# PWM_LOGIC.net
KiCad netlist of a schematic drawn in Altium Designer
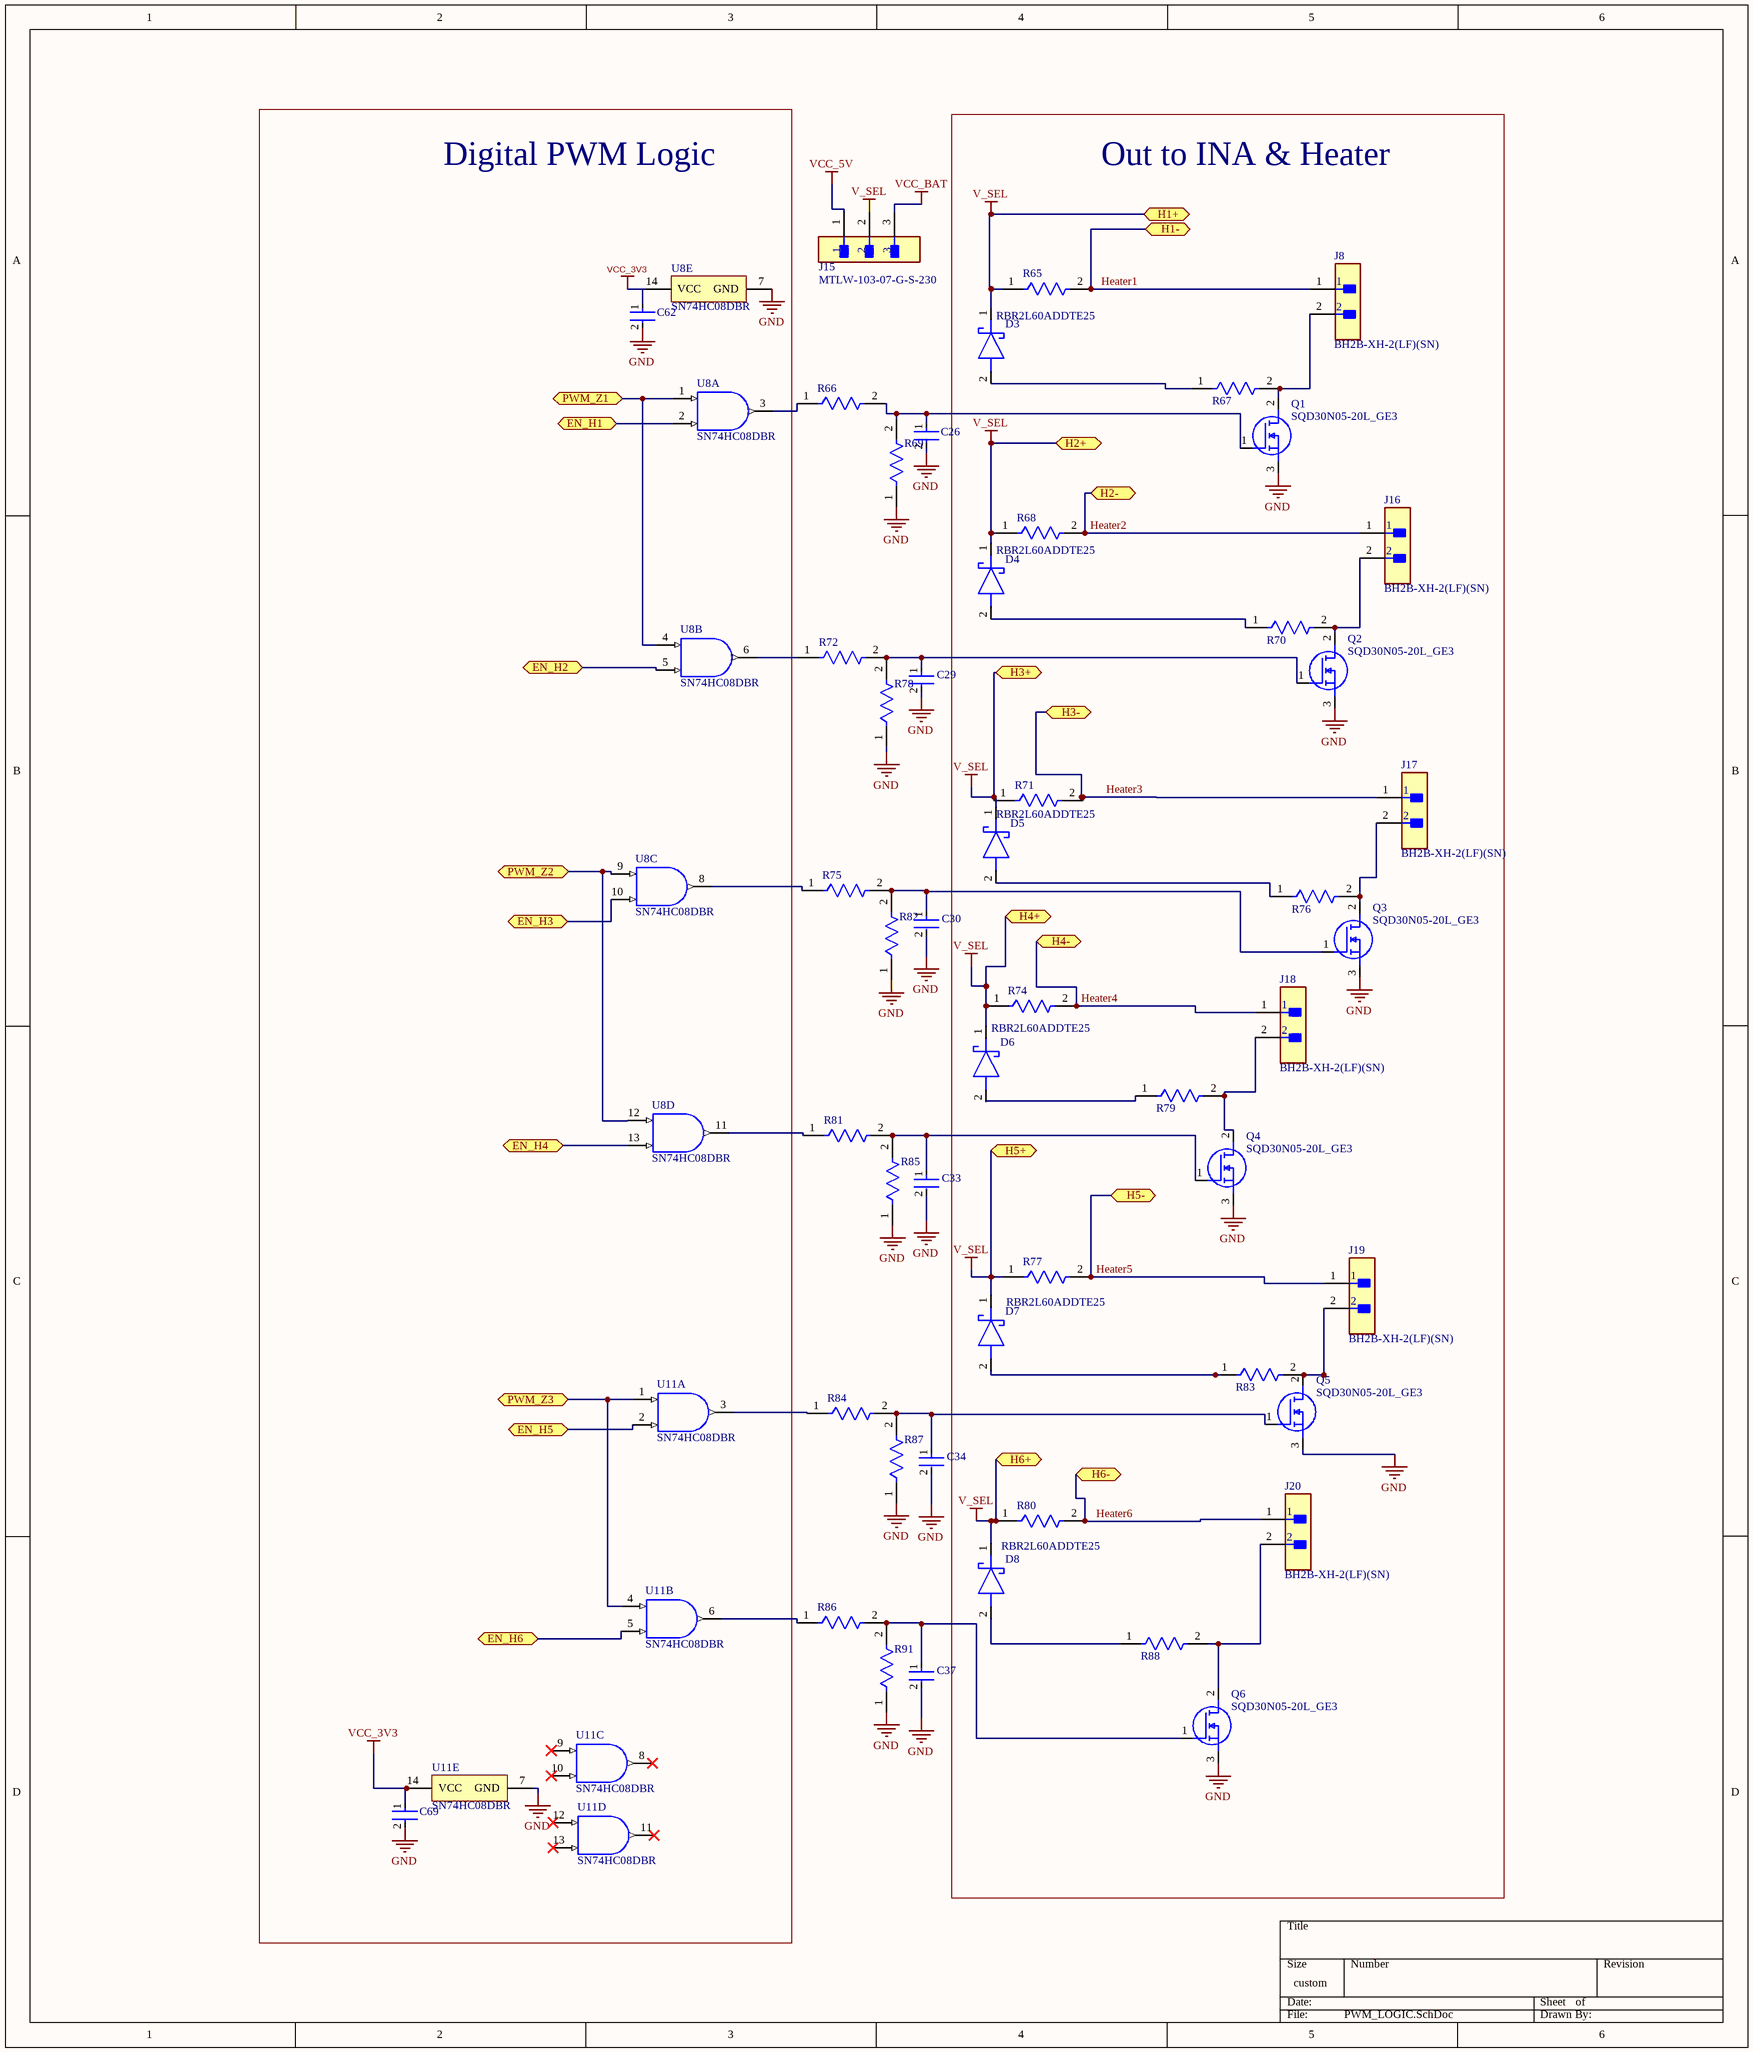
[diagram p0: PWM_LOGIC.SchDoc]

(export (version "E")
  (design (tool "Eeschema 10.0.6"))
  (components
    (comp (ref "C26")
      (value "C0603C472K3RACAUTO")
      (footprint "FP-C0603C-CF-MFG")
      (description "C0603 4,700 pF X7R 30ppm/°C 10.00% 25 V")
      (fields
        (field (name "TOLERANCE") "0.1")
        (field (name "OCTOPART") "https://octopart.com/c0603c472k3racauto-kemet-22128797")
      )
      (libsource (lib "Altium Content Vault") (part "b4654b650e69147ec39a6b967a45e02"))
    )
    (comp (ref "C29")
      (value "C0603C472K3RACAUTO")
      (footprint "FP-C0603C-CF-MFG")
      (description "C0603 4,700 pF X7R 30ppm/°C 10.00% 25 V")
      (fields
        (field (name "TOLERANCE") "0.1")
        (field (name "OCTOPART") "https://octopart.com/c0603c472k3racauto-kemet-22128797")
      )
      (libsource (lib "Altium Content Vault") (part "b4654b650e69147ec39a6b967a45e02"))
    )
    (comp (ref "C30")
      (value "C0603C472K3RACAUTO")
      (footprint "FP-C0603C-CF-MFG")
      (description "C0603 4,700 pF X7R 30ppm/°C 10.00% 25 V")
      (fields
        (field (name "TOLERANCE") "0.1")
        (field (name "OCTOPART") "https://octopart.com/c0603c472k3racauto-kemet-22128797")
      )
      (libsource (lib "Altium Content Vault") (part "b4654b650e69147ec39a6b967a45e02"))
    )
    (comp (ref "C33")
      (value "C0603C472K3RACAUTO")
      (footprint "FP-C0603C-CF-MFG")
      (description "C0603 4,700 pF X7R 30ppm/°C 10.00% 25 V")
      (fields
        (field (name "TOLERANCE") "0.1")
        (field (name "OCTOPART") "https://octopart.com/c0603c472k3racauto-kemet-22128797")
      )
      (libsource (lib "Altium Content Vault") (part "b4654b650e69147ec39a6b967a45e02"))
    )
    (comp (ref "C34")
      (value "C0603C472K3RACAUTO")
      (footprint "FP-C0603C-CF-MFG")
      (description "C0603 4,700 pF X7R 30ppm/°C 10.00% 25 V")
      (fields
        (field (name "TOLERANCE") "0.1")
        (field (name "OCTOPART") "https://octopart.com/c0603c472k3racauto-kemet-22128797")
      )
      (libsource (lib "Altium Content Vault") (part "b4654b650e69147ec39a6b967a45e02"))
    )
    (comp (ref "C37")
      (value "C0603C472K3RACAUTO")
      (footprint "FP-C0603C-CF-MFG")
      (description "C0603 4,700 pF X7R 30ppm/°C 10.00% 25 V")
      (fields
        (field (name "TOLERANCE") "0.1")
        (field (name "OCTOPART") "https://octopart.com/c0603c472k3racauto-kemet-22128797")
      )
      (libsource (lib "Altium Content Vault") (part "b4654b650e69147ec39a6b967a45e02"))
    )
    (comp (ref "C62")
      (value "GRM033C71A104KE14J")
      (footprint "FP-GRM033-0_03-MFG")
      (description "Chip Multilayer Ceramic Capacitors for General Purpose, 0201, 0.10uF, X7S, 22%, 10%, 10V")
      (fields (field (name "TOLERANCE") "10%"))
      (libsource (lib "Altium Content Vault") (part "b4654b650e69147ec39a6b967a45e02"))
    )
    (comp (ref "C69")
      (value "GRM033C71A104KE14J")
      (footprint "FP-GRM033-0_03-MFG")
      (description "Chip Multilayer Ceramic Capacitors for General Purpose, 0201, 0.10uF, X7S, 22%, 10%, 10V")
      (fields (field (name "TOLERANCE") "10%"))
      (libsource (lib "Altium Content Vault") (part "b4654b650e69147ec39a6b967a45e02"))
    )
    (comp (ref "D3")
      (value "RBR2L60ADDTE25")
      (footprint "SamacSys:DIOM5026X220N")
      (description "Schottky Diode")
      (fields (field (name "MOUSER PART NUMBER") "755-RBR2L60ADDTE25"))
      (libsource (lib "*") (part "RBR2L60ADDTE25"))
    )
    (comp (ref "D4")
      (value "RBR2L60ADDTE25")
      (footprint "SamacSys:DIOM5026X220N")
      (description "Schottky Diode")
      (fields (field (name "MOUSER PART NUMBER") "755-RBR2L60ADDTE25"))
      (libsource (lib "*") (part "RBR2L60ADDTE25"))
    )
    (comp (ref "D5")
      (value "RBR2L60ADDTE25")
      (footprint "SamacSys:DIOM5026X220N")
      (description "Schottky Diode")
      (fields (field (name "MOUSER PART NUMBER") "755-RBR2L60ADDTE25"))
      (libsource (lib "*") (part "RBR2L60ADDTE25"))
    )
    (comp (ref "D6")
      (value "RBR2L60ADDTE25")
      (footprint "SamacSys:DIOM5026X220N")
      (description "Schottky Diode")
      (fields (field (name "MOUSER PART NUMBER") "755-RBR2L60ADDTE25"))
      (libsource (lib "*") (part "RBR2L60ADDTE25"))
    )
    (comp (ref "D7")
      (value "RBR2L60ADDTE25")
      (footprint "SamacSys:DIOM5026X220N")
      (description "Schottky Diode")
      (fields (field (name "MOUSER PART NUMBER") "755-RBR2L60ADDTE25"))
      (libsource (lib "*") (part "RBR2L60ADDTE25"))
    )
    (comp (ref "D8")
      (value "RBR2L60ADDTE25")
      (footprint "SamacSys:DIOM5026X220N")
      (description "Schottky Diode")
      (fields (field (name "MOUSER PART NUMBER") "755-RBR2L60ADDTE25"))
      (libsource (lib "*") (part "RBR2L60ADDTE25"))
    )
    (comp (ref "J8")
      (value "BH2B-XH-2(LF)(SN)")
      (footprint "FP-BH2B-XH-2_LF_SN-MFG")
      (description "CONN HEADER VERT 2POS 2.5MM")
      (libsource (lib "Altium Content Vault") (part "3bc925449376181038e59eaffc5286c"))
    )
    (comp (ref "J15")
      (value "MTLW-103-07-G-S-230")
      (footprint "FP-MTLW-103-07-G-S-230-MFG")
      (description "CONN HEADER VERT 3POS 2.54MM")
      (libsource (lib "Altium Content Vault") (part "0d3f023dd272f625e17a2be33dea85f"))
    )
    (comp (ref "J16")
      (value "BH2B-XH-2(LF)(SN)")
      (footprint "FP-BH2B-XH-2_LF_SN-MFG")
      (description "CONN HEADER VERT 2POS 2.5MM")
      (libsource (lib "Altium Content Vault") (part "3bc925449376181038e59eaffc5286c"))
    )
    (comp (ref "J17")
      (value "BH2B-XH-2(LF)(SN)")
      (footprint "FP-BH2B-XH-2_LF_SN-MFG")
      (description "CONN HEADER VERT 2POS 2.5MM")
      (libsource (lib "Altium Content Vault") (part "3bc925449376181038e59eaffc5286c"))
    )
    (comp (ref "J18")
      (value "BH2B-XH-2(LF)(SN)")
      (footprint "FP-BH2B-XH-2_LF_SN-MFG")
      (description "CONN HEADER VERT 2POS 2.5MM")
      (libsource (lib "Altium Content Vault") (part "3bc925449376181038e59eaffc5286c"))
    )
    (comp (ref "J19")
      (value "BH2B-XH-2(LF)(SN)")
      (footprint "FP-BH2B-XH-2_LF_SN-MFG")
      (description "CONN HEADER VERT 2POS 2.5MM")
      (libsource (lib "Altium Content Vault") (part "3bc925449376181038e59eaffc5286c"))
    )
    (comp (ref "J20")
      (value "BH2B-XH-2(LF)(SN)")
      (footprint "FP-BH2B-XH-2_LF_SN-MFG")
      (description "CONN HEADER VERT 2POS 2.5MM")
      (libsource (lib "Altium Content Vault") (part "3bc925449376181038e59eaffc5286c"))
    )
    (comp (ref "Q1")
      (value "SQD30N05-20L_GE3")
      (footprint "SamacSys:SQD30N0520L_GE3")
      (description "MOSFET (N-Channel)")
      (fields (field (name "MOUSER PART NUMBER") "78-SQD30N05-20L_GE3"))
      (libsource (lib "*") (part "SQD30N05-20L_GE3"))
    )
    (comp (ref "Q2")
      (value "SQD30N05-20L_GE3")
      (footprint "SamacSys:SQD30N0520L_GE3")
      (description "MOSFET (N-Channel)")
      (fields (field (name "MOUSER PART NUMBER") "78-SQD30N05-20L_GE3"))
      (libsource (lib "*") (part "SQD30N05-20L_GE3"))
    )
    (comp (ref "Q3")
      (value "SQD30N05-20L_GE3")
      (footprint "SamacSys:SQD30N0520L_GE3")
      (description "MOSFET (N-Channel)")
      (fields (field (name "MOUSER PART NUMBER") "78-SQD30N05-20L_GE3"))
      (libsource (lib "*") (part "SQD30N05-20L_GE3"))
    )
    (comp (ref "Q4")
      (value "SQD30N05-20L_GE3")
      (footprint "SamacSys:SQD30N0520L_GE3")
      (description "MOSFET (N-Channel)")
      (fields (field (name "MOUSER PART NUMBER") "78-SQD30N05-20L_GE3"))
      (libsource (lib "*") (part "SQD30N05-20L_GE3"))
    )
    (comp (ref "Q5")
      (value "SQD30N05-20L_GE3")
      (footprint "SamacSys:SQD30N0520L_GE3")
      (description "MOSFET (N-Channel)")
      (fields (field (name "MOUSER PART NUMBER") "78-SQD30N05-20L_GE3"))
      (libsource (lib "*") (part "SQD30N05-20L_GE3"))
    )
    (comp (ref "Q6")
      (value "SQD30N05-20L_GE3")
      (footprint "SamacSys:SQD30N0520L_GE3")
      (description "MOSFET (N-Channel)")
      (fields (field (name "MOUSER PART NUMBER") "78-SQD30N05-20L_GE3"))
      (libsource (lib "*") (part "SQD30N05-20L_GE3"))
    )
    (comp (ref "R65")
      (value "CSR1206FT50L0")
      (footprint "FP-CSR1206-IPC_B")
      (description "General Purpose Thick Film Chip Resistor, 1206, 50mΩ, 1%, 100ppm/°C, 0.5W")
      (fields (field (name "TOLERANCE") "1%"))
      (libsource (lib "Altium Content Vault") (part "1029c3af85768c4190bb7ad29bc67b5"))
    )
    (comp (ref "R66")
      (value "RMCF1210FT330R")
      (footprint "FP-RMCF1210-IPC_B")
      (description "330Ω ±1% 0.5W 1210 Thick Film Chip Resistor AEC-Q200 compliant")
      (fields (field (name "TOLERANCE") "1%"))
      (libsource (lib "Altium Content Vault") (part "1029c3af85768c4190bb7ad29bc67b5"))
    )
    (comp (ref "R67")
      (value "ESR03EZPF75R0")
      (footprint "FP-ESR03-IPC_B")
      (description "75Ω ±1% 0.25W 0603 Anti-Surge Chip Resistor AEC-Q200")
      (fields (field (name "TOLERANCE") "1%"))
      (libsource (lib "Altium Content Vault") (part "1029c3af85768c4190bb7ad29bc67b5"))
    )
    (comp (ref "R68")
      (value "CSR1206FT50L0")
      (footprint "FP-CSR1206-IPC_B")
      (description "General Purpose Thick Film Chip Resistor, 1206, 50mΩ, 1%, 100ppm/°C, 0.5W")
      (fields (field (name "TOLERANCE") "1%"))
      (libsource (lib "Altium Content Vault") (part "1029c3af85768c4190bb7ad29bc67b5"))
    )
    (comp (ref "R69")
      (value "RMCF1206FG10K0")
      (footprint "FP-RMCF1206-MFG")
      (description "10kΩ ±1% 0.25W 1206 Thick Film Chip Resistor AEC-Q200 compliant")
      (fields (field (name "TOLERANCE") "1%"))
      (libsource (lib "Altium Content Vault") (part "1029c3af85768c4190bb7ad29bc67b5"))
    )
    (comp (ref "R70")
      (value "ESR03EZPF75R0")
      (footprint "FP-ESR03-IPC_B")
      (description "75Ω ±1% 0.25W 0603 Anti-Surge Chip Resistor AEC-Q200")
      (fields (field (name "TOLERANCE") "1%"))
      (libsource (lib "Altium Content Vault") (part "1029c3af85768c4190bb7ad29bc67b5"))
    )
    (comp (ref "R71")
      (value "CSR1206FT50L0")
      (footprint "FP-CSR1206-IPC_B")
      (description "General Purpose Thick Film Chip Resistor, 1206, 50mΩ, 1%, 100ppm/°C, 0.5W")
      (fields (field (name "TOLERANCE") "1%"))
      (libsource (lib "Altium Content Vault") (part "1029c3af85768c4190bb7ad29bc67b5"))
    )
    (comp (ref "R72")
      (value "RMCF1210FT330R")
      (footprint "FP-RMCF1210-IPC_B")
      (description "330Ω ±1% 0.5W 1210 Thick Film Chip Resistor AEC-Q200 compliant")
      (fields (field (name "TOLERANCE") "1%"))
      (libsource (lib "Altium Content Vault") (part "1029c3af85768c4190bb7ad29bc67b5"))
    )
    (comp (ref "R74")
      (value "CSR1206FT50L0")
      (footprint "FP-CSR1206-IPC_B")
      (description "General Purpose Thick Film Chip Resistor, 1206, 50mΩ, 1%, 100ppm/°C, 0.5W")
      (fields (field (name "TOLERANCE") "1%"))
      (libsource (lib "Altium Content Vault") (part "1029c3af85768c4190bb7ad29bc67b5"))
    )
    (comp (ref "R75")
      (value "RMCF1210FT330R")
      (footprint "FP-RMCF1210-IPC_B")
      (description "330Ω ±1% 0.5W 1210 Thick Film Chip Resistor AEC-Q200 compliant")
      (fields (field (name "TOLERANCE") "1%"))
      (libsource (lib "Altium Content Vault") (part "1029c3af85768c4190bb7ad29bc67b5"))
    )
    (comp (ref "R76")
      (value "ESR03EZPF75R0")
      (footprint "FP-ESR03-IPC_B")
      (description "75Ω ±1% 0.25W 0603 Anti-Surge Chip Resistor AEC-Q200")
      (fields (field (name "TOLERANCE") "1%"))
      (libsource (lib "Altium Content Vault") (part "1029c3af85768c4190bb7ad29bc67b5"))
    )
    (comp (ref "R77")
      (value "CSR1206FT50L0")
      (footprint "FP-CSR1206-IPC_B")
      (description "General Purpose Thick Film Chip Resistor, 1206, 50mΩ, 1%, 100ppm/°C, 0.5W")
      (fields (field (name "TOLERANCE") "1%"))
      (libsource (lib "Altium Content Vault") (part "1029c3af85768c4190bb7ad29bc67b5"))
    )
    (comp (ref "R78")
      (value "RMCF1206FG10K0")
      (footprint "FP-RMCF1206-MFG")
      (description "10kΩ ±1% 0.25W 1206 Thick Film Chip Resistor AEC-Q200 compliant")
      (fields (field (name "TOLERANCE") "1%"))
      (libsource (lib "Altium Content Vault") (part "1029c3af85768c4190bb7ad29bc67b5"))
    )
    (comp (ref "R79")
      (value "ESR03EZPF75R0")
      (footprint "FP-ESR03-IPC_B")
      (description "75Ω ±1% 0.25W 0603 Anti-Surge Chip Resistor AEC-Q200")
      (fields (field (name "TOLERANCE") "1%"))
      (libsource (lib "Altium Content Vault") (part "1029c3af85768c4190bb7ad29bc67b5"))
    )
    (comp (ref "R80")
      (value "CSR1206FT50L0")
      (footprint "FP-CSR1206-IPC_B")
      (description "General Purpose Thick Film Chip Resistor, 1206, 50mΩ, 1%, 100ppm/°C, 0.5W")
      (fields (field (name "TOLERANCE") "1%"))
      (libsource (lib "Altium Content Vault") (part "1029c3af85768c4190bb7ad29bc67b5"))
    )
    (comp (ref "R81")
      (value "RMCF1210FT330R")
      (footprint "FP-RMCF1210-IPC_B")
      (description "330Ω ±1% 0.5W 1210 Thick Film Chip Resistor AEC-Q200 compliant")
      (fields (field (name "TOLERANCE") "1%"))
      (libsource (lib "Altium Content Vault") (part "1029c3af85768c4190bb7ad29bc67b5"))
    )
    (comp (ref "R82")
      (value "RMCF1206FG10K0")
      (footprint "FP-RMCF1206-MFG")
      (description "10kΩ ±1% 0.25W 1206 Thick Film Chip Resistor AEC-Q200 compliant")
      (fields (field (name "TOLERANCE") "1%"))
      (libsource (lib "Altium Content Vault") (part "1029c3af85768c4190bb7ad29bc67b5"))
    )
    (comp (ref "R83")
      (value "ESR03EZPF75R0")
      (footprint "FP-ESR03-IPC_B")
      (description "75Ω ±1% 0.25W 0603 Anti-Surge Chip Resistor AEC-Q200")
      (fields (field (name "TOLERANCE") "1%"))
      (libsource (lib "Altium Content Vault") (part "1029c3af85768c4190bb7ad29bc67b5"))
    )
    (comp (ref "R84")
      (value "RMCF1210FT330R")
      (footprint "FP-RMCF1210-IPC_B")
      (description "330Ω ±1% 0.5W 1210 Thick Film Chip Resistor AEC-Q200 compliant")
      (fields (field (name "TOLERANCE") "1%"))
      (libsource (lib "Altium Content Vault") (part "1029c3af85768c4190bb7ad29bc67b5"))
    )
    (comp (ref "R85")
      (value "RMCF1206FG10K0")
      (footprint "FP-RMCF1206-MFG")
      (description "10kΩ ±1% 0.25W 1206 Thick Film Chip Resistor AEC-Q200 compliant")
      (fields (field (name "TOLERANCE") "1%"))
      (libsource (lib "Altium Content Vault") (part "1029c3af85768c4190bb7ad29bc67b5"))
    )
    (comp (ref "R86")
      (value "RMCF1210FT330R")
      (footprint "FP-RMCF1210-IPC_B")
      (description "330Ω ±1% 0.5W 1210 Thick Film Chip Resistor AEC-Q200 compliant")
      (fields (field (name "TOLERANCE") "1%"))
      (libsource (lib "Altium Content Vault") (part "1029c3af85768c4190bb7ad29bc67b5"))
    )
    (comp (ref "R87")
      (value "RMCF1206FG10K0")
      (footprint "FP-RMCF1206-MFG")
      (description "10kΩ ±1% 0.25W 1206 Thick Film Chip Resistor AEC-Q200 compliant")
      (fields (field (name "TOLERANCE") "1%"))
      (libsource (lib "Altium Content Vault") (part "1029c3af85768c4190bb7ad29bc67b5"))
    )
    (comp (ref "R88")
      (value "ESR03EZPF75R0")
      (footprint "FP-ESR03-IPC_B")
      (description "75Ω ±1% 0.25W 0603 Anti-Surge Chip Resistor AEC-Q200")
      (fields (field (name "TOLERANCE") "1%"))
      (libsource (lib "Altium Content Vault") (part "1029c3af85768c4190bb7ad29bc67b5"))
    )
    (comp (ref "R91")
      (value "RMCF1206FG10K0")
      (footprint "FP-RMCF1206-MFG")
      (description "10kΩ ±1% 0.25W 1206 Thick Film Chip Resistor AEC-Q200 compliant")
      (fields (field (name "TOLERANCE") "1%"))
      (libsource (lib "Altium Content Vault") (part "1029c3af85768c4190bb7ad29bc67b5"))
    )
    (comp (ref "U8")
      (value "SN74HC08DBR")
      (footprint "DB0014A_L")
      (description "Quadruple 2-Input Positive-AND Gates, DB0014A, LARGE T&R")
      (fields
        (field (name "MANUFACTURER") "Texas Instruments")
        (field (name "GENERIC PART NUMBER") "SN74HC08")
      )
      (libsource (lib "Altium Content Vault") (part "TI-AND-4-2IN-14"))
    )
    (comp (ref "U11")
      (value "SN74HC08DBR")
      (footprint "DB0014A_L")
      (description "Quadruple 2-Input Positive-AND Gates, DB0014A, LARGE T&R")
      (fields
        (field (name "MANUFACTURER") "Texas Instruments")
        (field (name "GENERIC PART NUMBER") "SN74HC08")
      )
      (libsource (lib "Altium Content Vault") (part "TI-AND-4-2IN-14"))
    )
  )
  (nets
    (net (code "2") (name "/EN_H1") (class "Default")
      (node (ref "U8") (pin "2") (pinfunction "1B_2") (pintype "input"))
    )
    (net (code "3") (name "/EN_H2") (class "Default")
      (node (ref "U8") (pin "5") (pinfunction "2B_5") (pintype "input"))
    )
    (net (code "4") (name "/EN_H3") (class "Default")
      (node (ref "U8") (pin "10") (pinfunction "3B_10") (pintype "input"))
    )
    (net (code "5") (name "/EN_H4") (class "Default")
      (node (ref "U8") (pin "13") (pinfunction "4B_13") (pintype "input"))
    )
    (net (code "6") (name "/EN_H5") (class "Default")
      (node (ref "U11") (pin "2") (pinfunction "1B_2") (pintype "input"))
    )
    (net (code "7") (name "/EN_H6") (class "Default")
      (node (ref "U11") (pin "5") (pinfunction "2B_5") (pintype "input"))
    )
    (net (code "8") (name "/Heater1") (class "Default")
      (node (ref "J8") (pin "1") (pinfunction "1_1") (pintype "passive"))
      (node (ref "R65") (pin "2") (pinfunction "2_2") (pintype "passive"))
    )
    (net (code "9") (name "/Heater2") (class "Default")
      (node (ref "J16") (pin "1") (pinfunction "1_1") (pintype "passive"))
      (node (ref "R68") (pin "2") (pinfunction "2_2") (pintype "passive"))
    )
    (net (code "10") (name "/Heater3") (class "Default")
      (node (ref "J17") (pin "1") (pinfunction "1_1") (pintype "passive"))
      (node (ref "R71") (pin "2") (pinfunction "2_2") (pintype "passive"))
    )
    (net (code "11") (name "/Heater4") (class "Default")
      (node (ref "J18") (pin "1") (pinfunction "1_1") (pintype "passive"))
      (node (ref "R74") (pin "2") (pinfunction "2_2") (pintype "passive"))
    )
    (net (code "12") (name "/Heater5") (class "Default")
      (node (ref "J19") (pin "1") (pinfunction "1_1") (pintype "passive"))
      (node (ref "R77") (pin "2") (pinfunction "2_2") (pintype "passive"))
    )
    (net (code "13") (name "/Heater6") (class "Default")
      (node (ref "J20") (pin "1") (pinfunction "1_1") (pintype "passive"))
      (node (ref "R80") (pin "2") (pinfunction "2_2") (pintype "passive"))
    )
    (net (code "14") (name "/PWM_Z1") (class "Default")
      (node (ref "U8") (pin "1") (pinfunction "1A_1") (pintype "input"))
      (node (ref "U8") (pin "4") (pinfunction "2A_4") (pintype "input"))
    )
    (net (code "15") (name "/PWM_Z2") (class "Default")
      (node (ref "U8") (pin "12") (pinfunction "4A_12") (pintype "input"))
      (node (ref "U8") (pin "9") (pinfunction "3A_9") (pintype "input"))
    )
    (net (code "16") (name "/PWM_Z3") (class "Default")
      (node (ref "U11") (pin "1") (pinfunction "1A_1") (pintype "input"))
      (node (ref "U11") (pin "4") (pinfunction "2A_4") (pintype "input"))
    )
    (net (code "17") (name "GND") (class "Default")
      (node (ref "C26") (pin "2") (pinfunction "2_2") (pintype "passive"))
      (node (ref "C29") (pin "2") (pinfunction "2_2") (pintype "passive"))
      (node (ref "C30") (pin "2") (pinfunction "2_2") (pintype "passive"))
      (node (ref "C33") (pin "2") (pinfunction "2_2") (pintype "passive"))
      (node (ref "C34") (pin "2") (pinfunction "2_2") (pintype "passive"))
      (node (ref "C37") (pin "2") (pinfunction "2_2") (pintype "passive"))
      (node (ref "C62") (pin "2") (pinfunction "2_2") (pintype "passive"))
      (node (ref "C69") (pin "2") (pinfunction "2_2") (pintype "passive"))
      (node (ref "Q1") (pin "3") (pinfunction "S_3") (pintype "passive"))
      (node (ref "Q2") (pin "3") (pinfunction "S_3") (pintype "passive"))
      (node (ref "Q3") (pin "3") (pinfunction "S_3") (pintype "passive"))
      (node (ref "Q4") (pin "3") (pinfunction "S_3") (pintype "passive"))
      (node (ref "Q5") (pin "3") (pinfunction "S_3") (pintype "passive"))
      (node (ref "Q6") (pin "3") (pinfunction "S_3") (pintype "passive"))
      (node (ref "R69") (pin "1") (pinfunction "1_1") (pintype "passive"))
      (node (ref "R78") (pin "1") (pinfunction "1_1") (pintype "passive"))
      (node (ref "R82") (pin "1") (pinfunction "1_1") (pintype "passive"))
      (node (ref "R85") (pin "1") (pinfunction "1_1") (pintype "passive"))
      (node (ref "R87") (pin "1") (pinfunction "1_1") (pintype "passive"))
      (node (ref "R91") (pin "1") (pinfunction "1_1") (pintype "passive"))
      (node (ref "U11") (pin "7") (pinfunction "GND_7") (pintype "power_in"))
      (node (ref "U8") (pin "7") (pinfunction "GND_7") (pintype "power_in"))
    )
    (net (code "18") (name "Net-(D3-A)") (class "Default")
      (node (ref "D3") (pin "2") (pinfunction "A_2") (pintype "passive"))
      (node (ref "R67") (pin "1") (pinfunction "1_1") (pintype "passive"))
    )
    (net (code "19") (name "Net-(D4-A)") (class "Default")
      (node (ref "D4") (pin "2") (pinfunction "A_2") (pintype "passive"))
      (node (ref "R70") (pin "1") (pinfunction "1_1") (pintype "passive"))
    )
    (net (code "20") (name "Net-(D5-A)") (class "Default")
      (node (ref "D5") (pin "2") (pinfunction "A_2") (pintype "passive"))
      (node (ref "R76") (pin "1") (pinfunction "1_1") (pintype "passive"))
    )
    (net (code "21") (name "Net-(D6-A)") (class "Default")
      (node (ref "D6") (pin "2") (pinfunction "A_2") (pintype "passive"))
      (node (ref "R79") (pin "1") (pinfunction "1_1") (pintype "passive"))
    )
    (net (code "22") (name "Net-(D7-A)") (class "Default")
      (node (ref "D7") (pin "2") (pinfunction "A_2") (pintype "passive"))
      (node (ref "R83") (pin "1") (pinfunction "1_1") (pintype "passive"))
    )
    (net (code "23") (name "Net-(D8-A)") (class "Default")
      (node (ref "D8") (pin "2") (pinfunction "A_2") (pintype "passive"))
      (node (ref "R88") (pin "1") (pinfunction "1_1") (pintype "passive"))
    )
    (net (code "24") (name "Net-(Q1-D)") (class "Default")
      (node (ref "J8") (pin "2") (pinfunction "2_2") (pintype "passive"))
      (node (ref "Q1") (pin "2") (pinfunction "D_2") (pintype "passive"))
      (node (ref "R67") (pin "2") (pinfunction "2_2") (pintype "passive"))
    )
    (net (code "25") (name "Net-(Q1-G)") (class "Default")
      (node (ref "C26") (pin "1") (pinfunction "1_1") (pintype "passive"))
      (node (ref "Q1") (pin "1") (pinfunction "G_1") (pintype "passive"))
      (node (ref "R66") (pin "2") (pinfunction "2_2") (pintype "passive"))
      (node (ref "R69") (pin "2") (pinfunction "2_2") (pintype "passive"))
    )
    (net (code "26") (name "Net-(Q2-D)") (class "Default")
      (node (ref "J16") (pin "2") (pinfunction "2_2") (pintype "passive"))
      (node (ref "Q2") (pin "2") (pinfunction "D_2") (pintype "passive"))
      (node (ref "R70") (pin "2") (pinfunction "2_2") (pintype "passive"))
    )
    (net (code "27") (name "Net-(Q2-G)") (class "Default")
      (node (ref "C29") (pin "1") (pinfunction "1_1") (pintype "passive"))
      (node (ref "Q2") (pin "1") (pinfunction "G_1") (pintype "passive"))
      (node (ref "R72") (pin "2") (pinfunction "2_2") (pintype "passive"))
      (node (ref "R78") (pin "2") (pinfunction "2_2") (pintype "passive"))
    )
    (net (code "28") (name "Net-(Q3-D)") (class "Default")
      (node (ref "J17") (pin "2") (pinfunction "2_2") (pintype "passive"))
      (node (ref "Q3") (pin "2") (pinfunction "D_2") (pintype "passive"))
      (node (ref "R76") (pin "2") (pinfunction "2_2") (pintype "passive"))
    )
    (net (code "29") (name "Net-(Q3-G)") (class "Default")
      (node (ref "C30") (pin "1") (pinfunction "1_1") (pintype "passive"))
      (node (ref "Q3") (pin "1") (pinfunction "G_1") (pintype "passive"))
      (node (ref "R75") (pin "2") (pinfunction "2_2") (pintype "passive"))
      (node (ref "R82") (pin "2") (pinfunction "2_2") (pintype "passive"))
    )
    (net (code "30") (name "Net-(Q4-D)") (class "Default")
      (node (ref "J18") (pin "2") (pinfunction "2_2") (pintype "passive"))
      (node (ref "Q4") (pin "2") (pinfunction "D_2") (pintype "passive"))
      (node (ref "R79") (pin "2") (pinfunction "2_2") (pintype "passive"))
    )
    (net (code "31") (name "Net-(Q4-G)") (class "Default")
      (node (ref "C33") (pin "1") (pinfunction "1_1") (pintype "passive"))
      (node (ref "Q4") (pin "1") (pinfunction "G_1") (pintype "passive"))
      (node (ref "R81") (pin "2") (pinfunction "2_2") (pintype "passive"))
      (node (ref "R85") (pin "2") (pinfunction "2_2") (pintype "passive"))
    )
    (net (code "32") (name "Net-(Q5-D)") (class "Default")
      (node (ref "J19") (pin "2") (pinfunction "2_2") (pintype "passive"))
      (node (ref "Q5") (pin "2") (pinfunction "D_2") (pintype "passive"))
      (node (ref "R83") (pin "2") (pinfunction "2_2") (pintype "passive"))
    )
    (net (code "33") (name "Net-(Q5-G)") (class "Default")
      (node (ref "C34") (pin "1") (pinfunction "1_1") (pintype "passive"))
      (node (ref "Q5") (pin "1") (pinfunction "G_1") (pintype "passive"))
      (node (ref "R84") (pin "2") (pinfunction "2_2") (pintype "passive"))
      (node (ref "R87") (pin "2") (pinfunction "2_2") (pintype "passive"))
    )
    (net (code "34") (name "Net-(Q6-D)") (class "Default")
      (node (ref "J20") (pin "2") (pinfunction "2_2") (pintype "passive"))
      (node (ref "Q6") (pin "2") (pinfunction "D_2") (pintype "passive"))
      (node (ref "R88") (pin "2") (pinfunction "2_2") (pintype "passive"))
    )
    (net (code "35") (name "Net-(Q6-G)") (class "Default")
      (node (ref "C37") (pin "1") (pinfunction "1_1") (pintype "passive"))
      (node (ref "Q6") (pin "1") (pinfunction "G_1") (pintype "passive"))
      (node (ref "R86") (pin "2") (pinfunction "2_2") (pintype "passive"))
      (node (ref "R91") (pin "2") (pinfunction "2_2") (pintype "passive"))
    )
    (net (code "36") (name "Net-(U8A-1Y)") (class "Default")
      (node (ref "R66") (pin "1") (pinfunction "1_1") (pintype "passive"))
      (node (ref "U8") (pin "3") (pinfunction "1Y_3") (pintype "output"))
    )
    (net (code "37") (name "Net-(U8B-2Y)") (class "Default")
      (node (ref "R72") (pin "1") (pinfunction "1_1") (pintype "passive"))
      (node (ref "U8") (pin "6") (pinfunction "2Y_6") (pintype "output"))
    )
    (net (code "38") (name "Net-(U8C-3Y)") (class "Default")
      (node (ref "R75") (pin "1") (pinfunction "1_1") (pintype "passive"))
      (node (ref "U8") (pin "8") (pinfunction "3Y_8") (pintype "output"))
    )
    (net (code "39") (name "Net-(U8D-4Y)") (class "Default")
      (node (ref "R81") (pin "1") (pinfunction "1_1") (pintype "passive"))
      (node (ref "U8") (pin "11") (pinfunction "4Y_11") (pintype "output"))
    )
    (net (code "40") (name "Net-(U11A-1Y)") (class "Default")
      (node (ref "R84") (pin "1") (pinfunction "1_1") (pintype "passive"))
      (node (ref "U11") (pin "3") (pinfunction "1Y_3") (pintype "output"))
    )
    (net (code "41") (name "Net-(U11B-2Y)") (class "Default")
      (node (ref "R86") (pin "1") (pinfunction "1_1") (pintype "passive"))
      (node (ref "U11") (pin "6") (pinfunction "2Y_6") (pintype "output"))
    )
    (net (code "42") (name "VCC_3V3") (class "Default")
      (node (ref "C62") (pin "1") (pinfunction "1_1") (pintype "passive"))
      (node (ref "C69") (pin "1") (pinfunction "1_1") (pintype "passive"))
      (node (ref "U11") (pin "14") (pinfunction "VCC_14") (pintype "power_in"))
      (node (ref "U8") (pin "14") (pinfunction "VCC_14") (pintype "power_in"))
    )
    (net (code "43") (name "VCC_5V") (class "Default")
      (node (ref "J15") (pin "1") (pinfunction "1_1") (pintype "passive"))
    )
    (net (code "44") (name "VCC_BAT") (class "Default")
      (node (ref "J15") (pin "3") (pinfunction "3_3") (pintype "passive"))
    )
    (net (code "45") (name "V_SEL") (class "Default")
      (node (ref "D3") (pin "1") (pinfunction "K_1") (pintype "passive"))
      (node (ref "D4") (pin "1") (pinfunction "K_1") (pintype "passive"))
      (node (ref "D5") (pin "1") (pinfunction "K_1") (pintype "passive"))
      (node (ref "D6") (pin "1") (pinfunction "K_1") (pintype "passive"))
      (node (ref "D7") (pin "1") (pinfunction "K_1") (pintype "passive"))
      (node (ref "D8") (pin "1") (pinfunction "K_1") (pintype "passive"))
      (node (ref "J15") (pin "2") (pinfunction "2_2") (pintype "passive"))
      (node (ref "R65") (pin "1") (pinfunction "1_1") (pintype "passive"))
      (node (ref "R68") (pin "1") (pinfunction "1_1") (pintype "passive"))
      (node (ref "R71") (pin "1") (pinfunction "1_1") (pintype "passive"))
      (node (ref "R74") (pin "1") (pinfunction "1_1") (pintype "passive"))
      (node (ref "R77") (pin "1") (pinfunction "1_1") (pintype "passive"))
      (node (ref "R80") (pin "1") (pinfunction "1_1") (pintype "passive"))
    )
    (net (code "46") (name "unconnected-(U11C-3A-Pad9)") (class "Default")
      (node (ref "U11") (pin "9") (pinfunction "3A_9") (pintype "input+no_connect"))
    )
    (net (code "47") (name "unconnected-(U11C-3B-Pad10)") (class "Default")
      (node (ref "U11") (pin "10") (pinfunction "3B_10") (pintype "input+no_connect"))
    )
    (net (code "48") (name "unconnected-(U11C-3Y-Pad8)") (class "Default")
      (node (ref "U11") (pin "8") (pinfunction "3Y_8") (pintype "output+no_connect"))
    )
    (net (code "49") (name "unconnected-(U11D-4A-Pad12)") (class "Default")
      (node (ref "U11") (pin "12") (pinfunction "4A_12") (pintype "input+no_connect"))
    )
    (net (code "50") (name "unconnected-(U11D-4B-Pad13)") (class "Default")
      (node (ref "U11") (pin "13") (pinfunction "4B_13") (pintype "input+no_connect"))
    )
    (net (code "51") (name "unconnected-(U11D-4Y-Pad11)") (class "Default")
      (node (ref "U11") (pin "11") (pinfunction "4Y_11") (pintype "output+no_connect"))
    )
  )
)
